# respirhoCR2450.net
KiCad netlist of a schematic drawn in EAGLE
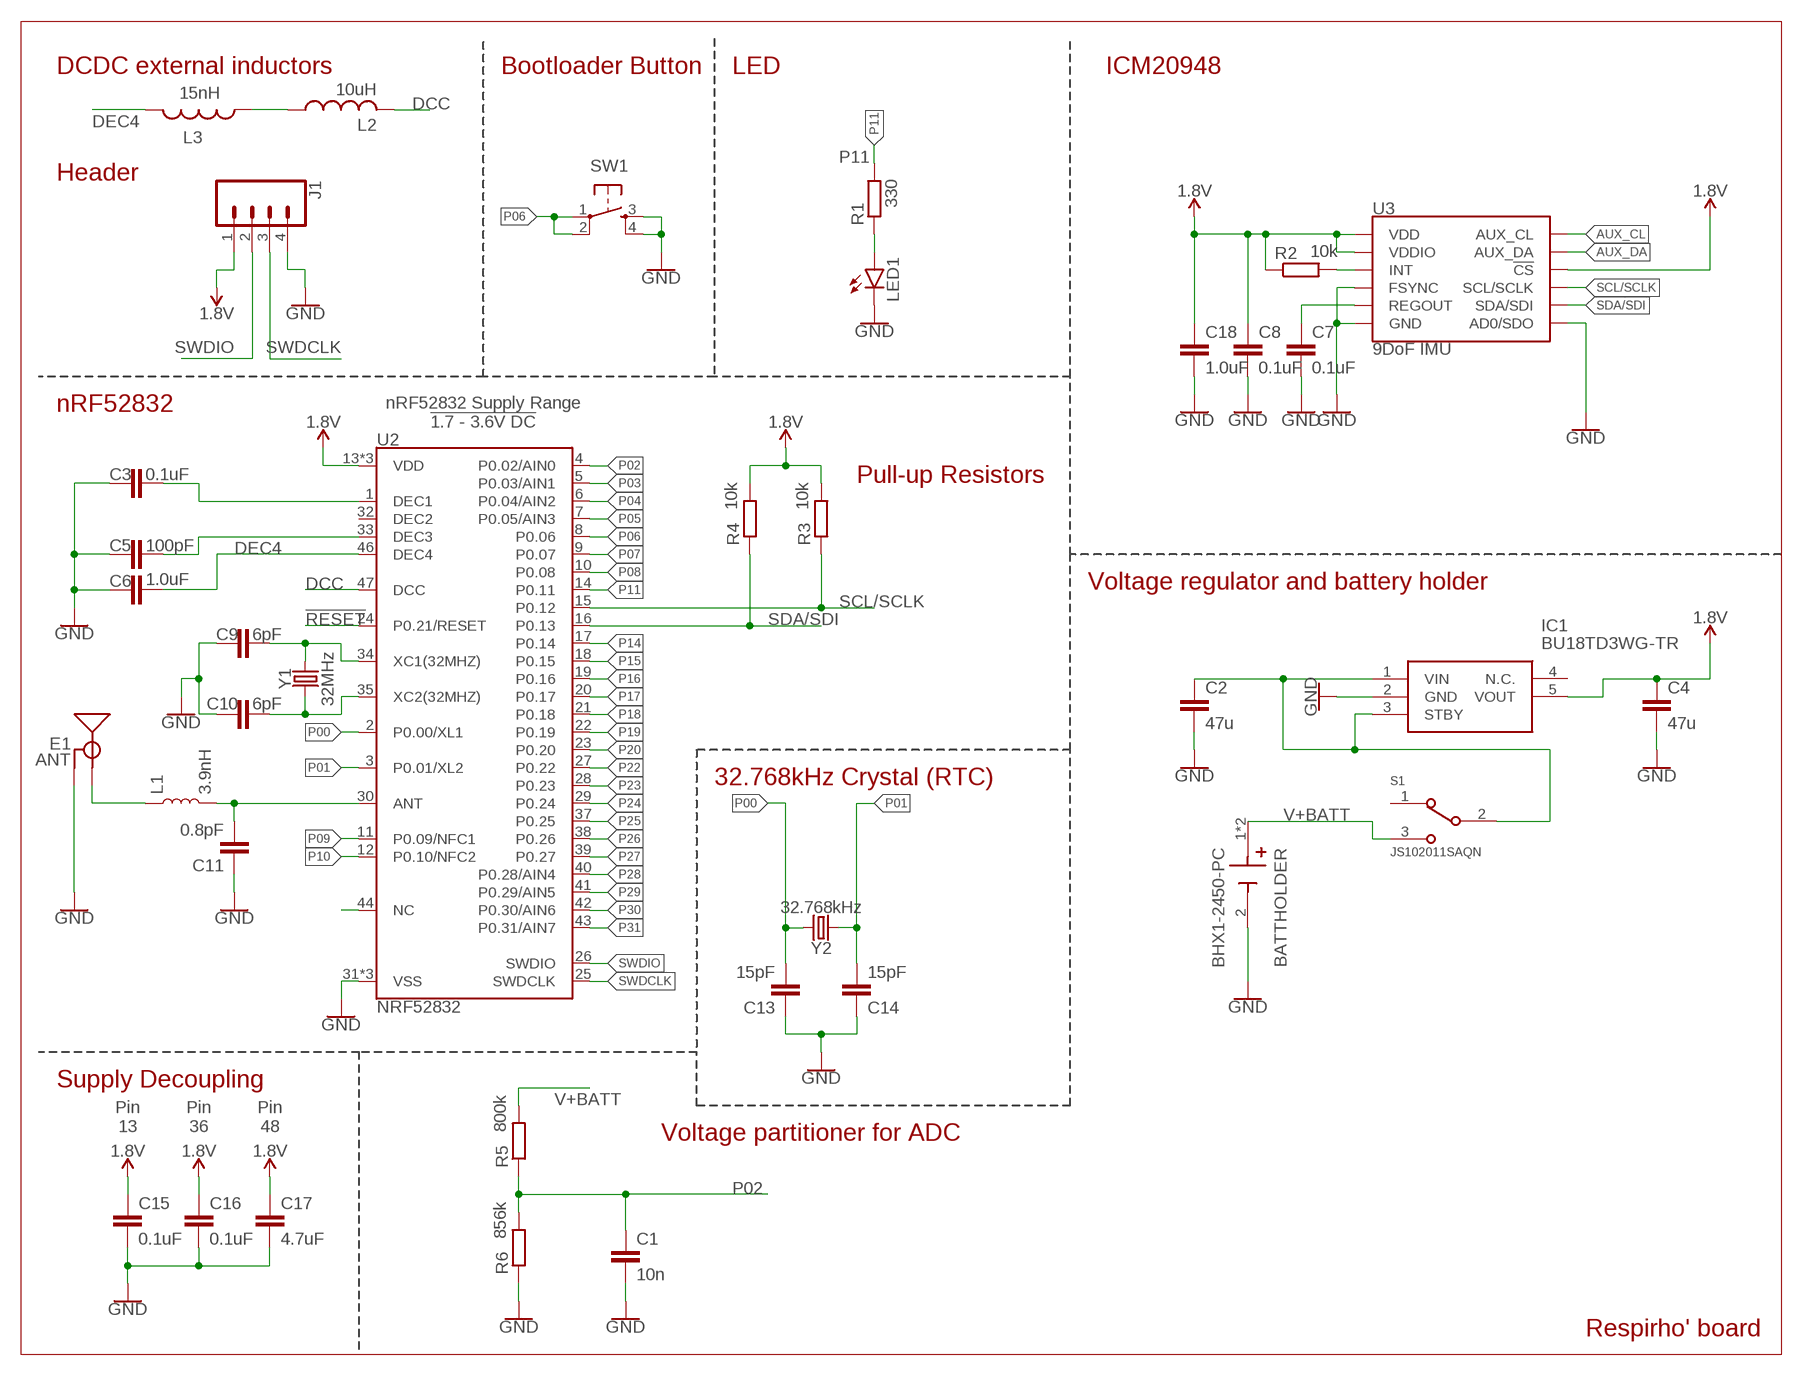
[diagram p0: schematic, sheet 1]

(export (version "E")
  (design (tool "Eeschema 10.0.6"))
  (components
    (comp (ref "BATTHOLDER")
      (value "BHX1-2450-PC")
      (footprint "eagle-import:BAT_BHX1-2450-PC")
      (fields (field (name "DIGI-KEY_PART_NUMBER") "BHX1-2450-PC-ND") (field (name "MF") "MPD"))
      (libsource (lib "eagle-import") (part "BHX1-2450-PC"))
    )
    (comp (ref "C1")
      (value "10n")
      (footprint "eagle-import:C1206")
      (libsource (lib "eagle-import") (part "C-EUC1206"))
    )
    (comp (ref "C2")
      (value "47u")
      (footprint "eagle-import:C1206")
      (libsource (lib "eagle-import") (part "C-EUC1206"))
    )
    (comp (ref "C3")
      (value "0.1uF")
      (footprint "eagle-import:0402")
      (libsource (lib "eagle-import") (part "0.1UF-0402-16V-10%"))
    )
    (comp (ref "C4")
      (value "47u")
      (footprint "eagle-import:C1206")
      (libsource (lib "eagle-import") (part "C-EUC1206"))
    )
    (comp (ref "C5")
      (value "100pF")
      (footprint "eagle-import:0402")
      (libsource (lib "eagle-import") (part "100PF-0402-50V-5%"))
    )
    (comp (ref "C6")
      (value "1.0uF")
      (footprint "eagle-import:0402")
      (libsource (lib "eagle-import") (part "1.0UF-0402-16V-10%"))
    )
    (comp (ref "C7")
      (value "0.1uF")
      (footprint "eagle-import:0603")
      (libsource (lib "eagle-import") (part "0.1UF-0603-25V-5%"))
    )
    (comp (ref "C8")
      (value "0.1uF")
      (footprint "eagle-import:0603")
      (libsource (lib "eagle-import") (part "0.1UF-0603-25V-5%"))
    )
    (comp (ref "C9")
      (value "6pF")
      (footprint "eagle-import:0402")
      (libsource (lib "eagle-import") (part "6PF-0402-50V-0.5%"))
    )
    (comp (ref "C10")
      (value "6pF")
      (footprint "eagle-import:0402")
      (libsource (lib "eagle-import") (part "6PF-0402-50V-0.5%"))
    )
    (comp (ref "C11")
      (value "0.8pF")
      (footprint "eagle-import:0402")
      (libsource (lib "eagle-import") (part "0.8PF-0402-50V-0.1PF"))
    )
    (comp (ref "C13")
      (value "15pF")
      (footprint "eagle-import:0402")
      (libsource (lib "eagle-import") (part "15PF-0402-50V-5%"))
    )
    (comp (ref "C14")
      (value "15pF")
      (footprint "eagle-import:0402")
      (libsource (lib "eagle-import") (part "15PF-0402-50V-5%"))
    )
    (comp (ref "C15")
      (value "0.1uF")
      (footprint "eagle-import:0402")
      (libsource (lib "eagle-import") (part "0.1UF-0402-16V-10%"))
    )
    (comp (ref "C16")
      (value "0.1uF")
      (footprint "eagle-import:0402")
      (libsource (lib "eagle-import") (part "0.1UF-0402-16V-10%"))
    )
    (comp (ref "C17")
      (value "4.7uF")
      (footprint "eagle-import:0603")
      (libsource (lib "eagle-import") (part "4.7UF0603"))
    )
    (comp (ref "C18")
      (value "1.0uF")
      (footprint "eagle-import:0603")
      (libsource (lib "eagle-import") (part "1.0UF-0603-16V-10%-X7R"))
    )
    (comp (ref "E1")
      (value "ANT")
      (footprint "eagle-import:TRACE_ANTENNA_2.4GHZ_15.2MM")
      (libsource (lib "eagle-import") (part "ANTENNA-GROUNDEDTRACE-15.2MM"))
    )
    (comp (ref "IC1")
      (value "BU18TD3WG-TR")
      (footprint "eagle-import:SOT95P280X125-5N")
      (fields (field (name "MOUSER_PART_NUMBER") "755-BU18TD3WG-TR"))
      (libsource (lib "eagle-import") (part "BU18TD3WG-TR"))
    )
    (comp (ref "J1")
      (value "CONN_04PTH")
      (footprint "eagle-import:1X04")
      (libsource (lib "eagle-import") (part "CONN_04PTH"))
    )
    (comp (ref "L1")
      (value "3.9nH")
      (footprint "eagle-import:0402")
      (libsource (lib "eagle-import") (part "INDUCTOR-0402-3.9NH"))
    )
    (comp (ref "L2")
      (value "10uH")
      (footprint "eagle-import:RESC0603_L")
      (libsource (lib "eagle-import") (part "INDUCTOR_0603_L"))
    )
    (comp (ref "L3")
      (value "15nH")
      (footprint "eagle-import:INDC1005X55N")
      (fields
        (field (name "DIGI-KEY_PART_NUMBER") "490-2625-1-ND")
        (field (name "MF") "Murata Electronics")
        (field (name "MP") "LQG15HS15NJ02D")
      )
      (libsource (lib "eagle-import") (part "LQG15HS15NJ02D"))
    )
    (comp (ref "LED1")
      (value "LEDCHIPLED_1206")
      (footprint "eagle-import:CHIPLED_1206")
      (libsource (lib "eagle-import") (part "LEDCHIPLED_1206"))
    )
    (comp (ref "R1")
      (value "330")
      (footprint "eagle-import:R0805")
      (libsource (lib "eagle-import") (part "R-EU_R0805"))
    )
    (comp (ref "R2")
      (value "10k")
      (footprint "eagle-import:R0805")
      (libsource (lib "eagle-import") (part "R-EU_R0805"))
    )
    (comp (ref "R3")
      (value "10k")
      (footprint "eagle-import:R0805")
      (libsource (lib "eagle-import") (part "R-EU_R0805"))
    )
    (comp (ref "R4")
      (value "10k")
      (footprint "eagle-import:R0805")
      (libsource (lib "eagle-import") (part "R-EU_R0805"))
    )
    (comp (ref "R5")
      (value "800k")
      (footprint "eagle-import:R0805")
      (libsource (lib "eagle-import") (part "R-EU_R0805"))
    )
    (comp (ref "R6")
      (value "856k")
      (footprint "eagle-import:R0805")
      (libsource (lib "eagle-import") (part "R-EU_R0805"))
    )
    (comp (ref "S1")
      (value "JS102011SAQN")
      (footprint "eagle-import:SW_JS102011SAQN")
      (fields (field (name "DIGI-KEY_PART_NUMBER") "401-1999-1-ND") (field (name "MF") "C&K"))
      (libsource (lib "eagle-import") (part "JS102011SAQN"))
    )
    (comp (ref "SW1")
      (value "SWITCH_SPST_4_PINRECT")
      (footprint "eagle-import:TACTILE_SWITCH_SMD_4.6X2.8MM")
      (libsource (lib "eagle-import") (part "SWITCH_SPST_4_PINRECT"))
    )
    (comp (ref "U2")
      (value "NRF52832")
      (footprint "eagle-import:QFN48-6X6MM")
      (libsource (lib "eagle-import") (part "NRF52832"))
    )
    (comp (ref "U3")
      (value "9DoF IMU")
      (footprint "eagle-import:QFN24-3X3")
      (libsource (lib "eagle-import") (part "ICM-20948"))
    )
    (comp (ref "Y1")
      (value "32MHz")
      (footprint "eagle-import:CRYSTAL-SMD-2.0X1.6MM")
      (libsource (lib "eagle-import") (part "CRYSTAL-32MHZ-SMD-2.0X1.6MM"))
    )
    (comp (ref "Y2")
      (value "32.768kHz")
      (footprint "eagle-import:CRYSTAL-SMD-3.2X1.5MM")
      (libsource (lib "eagle-import") (part "CRYSTAL-32.768KHZSMD-3.2X1.5"))
    )
  )
  (nets
    (net (code "1") (name "/DCC") (class "Default")
      (node (ref "L2") (pin "2") (pinfunction "2_2") (pintype "passive"))
      (node (ref "U2") (pin "47") (pinfunction "DCC_47") (pintype "bidirectional"))
    )
    (net (code "2") (name "/DEC4") (class "Default")
      (node (ref "C6") (pin "2") (pinfunction "2_2") (pintype "passive"))
      (node (ref "L3") (pin "2") (pinfunction "2_2") (pintype "passive"))
      (node (ref "U2") (pin "46") (pinfunction "DEC4_46") (pintype "bidirectional"))
    )
    (net (code "3") (name "/V+BATT") (class "Default")
      (node (ref "BATTHOLDER") (pin "1") (pinfunction "+_1") (pintype "passive"))
      (node (ref "BATTHOLDER") (pin "1_1") (pinfunction "+_1_1") (pintype "passive"))
      (node (ref "R5") (pin "2") (pinfunction "2_2") (pintype "passive"))
      (node (ref "S1") (pin "3") (pinfunction "3_3") (pintype "passive"))
    )
    (net (code "4") (name "/~{RESET}") (class "Default")
      (node (ref "U2") (pin "24") (pinfunction "P0.21/RESET_24") (pintype "bidirectional"))
    )
    (net (code "5") (name "1.8V") (class "Default")
      (node (ref "C15") (pin "1") (pinfunction "1_1") (pintype "passive"))
      (node (ref "C16") (pin "1") (pinfunction "1_1") (pintype "passive"))
      (node (ref "C17") (pin "1") (pinfunction "1_1") (pintype "passive"))
      (node (ref "C18") (pin "1") (pinfunction "1_1") (pintype "passive"))
      (node (ref "C4") (pin "1") (pinfunction "1_1") (pintype "passive"))
      (node (ref "C8") (pin "1") (pinfunction "1_1") (pintype "passive"))
      (node (ref "IC1") (pin "5") (pinfunction "VOUT_5") (pintype "bidirectional"))
      (node (ref "J1") (pin "1") (pinfunction "1_1") (pintype "passive"))
      (node (ref "R2") (pin "1") (pinfunction "1_1") (pintype "passive"))
      (node (ref "R3") (pin "2") (pinfunction "2_2") (pintype "passive"))
      (node (ref "R4") (pin "2") (pinfunction "2_2") (pintype "passive"))
      (node (ref "U2") (pin "13") (pinfunction "VDD_13") (pintype "bidirectional"))
      (node (ref "U2") (pin "36") (pinfunction "VDD_36") (pintype "bidirectional"))
      (node (ref "U2") (pin "48") (pinfunction "VDD_48") (pintype "bidirectional"))
      (node (ref "U3") (pin "13") (pinfunction "VDD_13") (pintype "bidirectional"))
      (node (ref "U3") (pin "22") (pinfunction "~{CS}_22") (pintype "bidirectional"))
      (node (ref "U3") (pin "8") (pinfunction "VDDIO_8") (pintype "bidirectional"))
    )
    (net (code "6") (name "AUX_CL") (class "Default")
      (node (ref "U3") (pin "7") (pinfunction "AUX_CL_7") (pintype "bidirectional"))
    )
    (net (code "7") (name "AUX_DA") (class "Default")
      (node (ref "U3") (pin "21") (pinfunction "AUX_DA_21") (pintype "bidirectional"))
    )
    (net (code "8") (name "GND") (class "Default")
      (node (ref "BATTHOLDER") (pin "2") (pinfunction "-_2") (pintype "passive"))
      (node (ref "C1") (pin "2") (pinfunction "2_2") (pintype "passive"))
      (node (ref "C10") (pin "2") (pinfunction "2_2") (pintype "passive"))
      (node (ref "C11") (pin "1") (pinfunction "1_1") (pintype "passive"))
      (node (ref "C13") (pin "1") (pinfunction "1_1") (pintype "passive"))
      (node (ref "C14") (pin "1") (pinfunction "1_1") (pintype "passive"))
      (node (ref "C15") (pin "2") (pinfunction "2_2") (pintype "passive"))
      (node (ref "C16") (pin "2") (pinfunction "2_2") (pintype "passive"))
      (node (ref "C17") (pin "2") (pinfunction "2_2") (pintype "passive"))
      (node (ref "C18") (pin "2") (pinfunction "2_2") (pintype "passive"))
      (node (ref "C2") (pin "2") (pinfunction "2_2") (pintype "passive"))
      (node (ref "C3") (pin "1") (pinfunction "1_1") (pintype "passive"))
      (node (ref "C4") (pin "2") (pinfunction "2_2") (pintype "passive"))
      (node (ref "C5") (pin "1") (pinfunction "1_1") (pintype "passive"))
      (node (ref "C6") (pin "1") (pinfunction "1_1") (pintype "passive"))
      (node (ref "C7") (pin "2") (pinfunction "2_2") (pintype "passive"))
      (node (ref "C8") (pin "2") (pinfunction "2_2") (pintype "passive"))
      (node (ref "C9") (pin "1") (pinfunction "1_1") (pintype "passive"))
      (node (ref "E1") (pin "GND") (pinfunction "GND_GND") (pintype "bidirectional"))
      (node (ref "IC1") (pin "2") (pinfunction "GND_2") (pintype "bidirectional"))
      (node (ref "J1") (pin "4") (pinfunction "4_4") (pintype "passive"))
      (node (ref "LED1") (pin "C") (pinfunction "C_C") (pintype "passive"))
      (node (ref "R6") (pin "1") (pinfunction "1_1") (pintype "passive"))
      (node (ref "SW1") (pin "3") (pinfunction "3_3") (pintype "passive"))
      (node (ref "SW1") (pin "4") (pinfunction "4_4") (pintype "passive"))
      (node (ref "U2") (pin "31") (pinfunction "VSS_31") (pintype "bidirectional"))
      (node (ref "U2") (pin "45") (pinfunction "VSS_45") (pintype "bidirectional"))
      (node (ref "U2") (pin "EP") (pinfunction "VSS_EP") (pintype "bidirectional"))
      (node (ref "U3") (pin "11") (pinfunction "FSYNC_11") (pintype "bidirectional"))
      (node (ref "U3") (pin "18") (pinfunction "GND_18") (pintype "bidirectional"))
      (node (ref "U3") (pin "20") (pinfunction "GND_20") (pintype "bidirectional"))
      (node (ref "U3") (pin "9") (pinfunction "AD0/SDO_9") (pintype "bidirectional"))
    )
    (net (code "9") (name "Net-(E1-SIGNAL)") (class "Default")
      (node (ref "E1") (pin "ANT") (pinfunction "SIGNAL_ANT") (pintype "bidirectional"))
      (node (ref "L1") (pin "1") (pinfunction "1_1") (pintype "passive"))
    )
    (net (code "10") (name "Net-(IC1-STBY)") (class "Default")
      (node (ref "C2") (pin "1") (pinfunction "1_1") (pintype "passive"))
      (node (ref "IC1") (pin "1") (pinfunction "VIN_1") (pintype "bidirectional"))
      (node (ref "IC1") (pin "3") (pinfunction "STBY_3") (pintype "bidirectional"))
      (node (ref "S1") (pin "2") (pinfunction "2_2") (pintype "passive"))
    )
    (net (code "11") (name "Net-(L2-Pad1)") (class "Default")
      (node (ref "L2") (pin "1") (pinfunction "1_1") (pintype "passive"))
      (node (ref "L3") (pin "1") (pinfunction "1_1") (pintype "passive"))
    )
    (net (code "12") (name "Net-(LED1-PadA)") (class "Default")
      (node (ref "LED1") (pin "A") (pinfunction "A_A") (pintype "passive"))
      (node (ref "R1") (pin "1") (pinfunction "1_1") (pintype "passive"))
    )
    (net (code "13") (name "Net-(U2-ANT)") (class "Default")
      (node (ref "C11") (pin "2") (pinfunction "2_2") (pintype "passive"))
      (node (ref "L1") (pin "2") (pinfunction "2_2") (pintype "passive"))
      (node (ref "U2") (pin "30") (pinfunction "ANT_30") (pintype "bidirectional"))
    )
    (net (code "14") (name "Net-(U2-DEC1)") (class "Default")
      (node (ref "C3") (pin "2") (pinfunction "2_2") (pintype "passive"))
      (node (ref "U2") (pin "1") (pinfunction "DEC1_1") (pintype "bidirectional"))
    )
    (net (code "15") (name "Net-(U2-DEC3)") (class "Default")
      (node (ref "C5") (pin "2") (pinfunction "2_2") (pintype "passive"))
      (node (ref "U2") (pin "33") (pinfunction "DEC3_33") (pintype "bidirectional"))
    )
    (net (code "16") (name "Net-(U2-XC1(32MHZ))") (class "Default")
      (node (ref "C9") (pin "2") (pinfunction "2_2") (pintype "passive"))
      (node (ref "U2") (pin "34") (pinfunction "XC1(32MHZ)_34") (pintype "bidirectional"))
      (node (ref "Y1") (pin "3") (pinfunction "2_3") (pintype "passive"))
    )
    (net (code "17") (name "Net-(U2-XC2(32MHZ))") (class "Default")
      (node (ref "C10") (pin "1") (pinfunction "1_1") (pintype "passive"))
      (node (ref "U2") (pin "35") (pinfunction "XC2(32MHZ)_35") (pintype "bidirectional"))
      (node (ref "Y1") (pin "1") (pinfunction "1_1") (pintype "passive"))
    )
    (net (code "18") (name "Net-(U3-INT)") (class "Default")
      (node (ref "R2") (pin "2") (pinfunction "2_2") (pintype "passive"))
      (node (ref "U3") (pin "12") (pinfunction "INT_12") (pintype "bidirectional"))
    )
    (net (code "19") (name "Net-(U3-REGOUT)") (class "Default")
      (node (ref "C7") (pin "1") (pinfunction "1_1") (pintype "passive"))
      (node (ref "U3") (pin "10") (pinfunction "REGOUT_10") (pintype "bidirectional"))
    )
    (net (code "20") (name "P00") (class "Default")
      (node (ref "C13") (pin "2") (pinfunction "2_2") (pintype "passive"))
      (node (ref "U2") (pin "2") (pinfunction "P0.00/XL1_2") (pintype "bidirectional"))
      (node (ref "Y2") (pin "P$2") (pinfunction "2_P$2") (pintype "passive"))
    )
    (net (code "21") (name "P01") (class "Default")
      (node (ref "C14") (pin "2") (pinfunction "2_2") (pintype "passive"))
      (node (ref "U2") (pin "3") (pinfunction "P0.01/XL2_3") (pintype "bidirectional"))
      (node (ref "Y2") (pin "P$1") (pinfunction "1_P$1") (pintype "passive"))
    )
    (net (code "22") (name "P02") (class "Default")
      (node (ref "C1") (pin "1") (pinfunction "1_1") (pintype "passive"))
      (node (ref "R5") (pin "1") (pinfunction "1_1") (pintype "passive"))
      (node (ref "R6") (pin "2") (pinfunction "2_2") (pintype "passive"))
      (node (ref "U2") (pin "4") (pinfunction "P0.02/AIN0_4") (pintype "bidirectional"))
    )
    (net (code "23") (name "P03") (class "Default")
      (node (ref "U2") (pin "5") (pinfunction "P0.03/AIN1_5") (pintype "bidirectional"))
    )
    (net (code "24") (name "P04") (class "Default")
      (node (ref "U2") (pin "6") (pinfunction "P0.04/AIN2_6") (pintype "bidirectional"))
    )
    (net (code "25") (name "P05") (class "Default")
      (node (ref "U2") (pin "7") (pinfunction "P0.05/AIN3_7") (pintype "bidirectional"))
    )
    (net (code "26") (name "P06") (class "Default")
      (node (ref "SW1") (pin "1") (pinfunction "1_1") (pintype "passive"))
      (node (ref "SW1") (pin "2") (pinfunction "2_2") (pintype "passive"))
      (node (ref "U2") (pin "8") (pinfunction "P0.06_8") (pintype "bidirectional"))
    )
    (net (code "27") (name "P07") (class "Default")
      (node (ref "U2") (pin "9") (pinfunction "P0.07_9") (pintype "bidirectional"))
    )
    (net (code "28") (name "P08") (class "Default")
      (node (ref "U2") (pin "10") (pinfunction "P0.08_10") (pintype "bidirectional"))
    )
    (net (code "29") (name "P09") (class "Default")
      (node (ref "U2") (pin "11") (pinfunction "P0.09/NFC1_11") (pintype "bidirectional"))
    )
    (net (code "30") (name "P10") (class "Default")
      (node (ref "U2") (pin "12") (pinfunction "P0.10/NFC2_12") (pintype "bidirectional"))
    )
    (net (code "31") (name "P11") (class "Default")
      (node (ref "R1") (pin "2") (pinfunction "2_2") (pintype "passive"))
      (node (ref "U2") (pin "14") (pinfunction "P0.11_14") (pintype "bidirectional"))
    )
    (net (code "32") (name "P14") (class "Default")
      (node (ref "U2") (pin "17") (pinfunction "P0.14_17") (pintype "bidirectional"))
    )
    (net (code "33") (name "P15") (class "Default")
      (node (ref "U2") (pin "18") (pinfunction "P0.15_18") (pintype "bidirectional"))
    )
    (net (code "34") (name "P16") (class "Default")
      (node (ref "U2") (pin "19") (pinfunction "P0.16_19") (pintype "bidirectional"))
    )
    (net (code "35") (name "P17") (class "Default")
      (node (ref "U2") (pin "20") (pinfunction "P0.17_20") (pintype "bidirectional"))
    )
    (net (code "36") (name "P18") (class "Default")
      (node (ref "U2") (pin "21") (pinfunction "P0.18_21") (pintype "bidirectional"))
    )
    (net (code "37") (name "P19") (class "Default")
      (node (ref "U2") (pin "22") (pinfunction "P0.19_22") (pintype "bidirectional"))
    )
    (net (code "38") (name "P20") (class "Default")
      (node (ref "U2") (pin "23") (pinfunction "P0.20_23") (pintype "bidirectional"))
    )
    (net (code "39") (name "P22") (class "Default")
      (node (ref "U2") (pin "27") (pinfunction "P0.22_27") (pintype "bidirectional"))
    )
    (net (code "40") (name "P23") (class "Default")
      (node (ref "U2") (pin "28") (pinfunction "P0.23_28") (pintype "bidirectional"))
    )
    (net (code "41") (name "P24") (class "Default")
      (node (ref "U2") (pin "29") (pinfunction "P0.24_29") (pintype "bidirectional"))
    )
    (net (code "42") (name "P25") (class "Default")
      (node (ref "U2") (pin "37") (pinfunction "P0.25_37") (pintype "bidirectional"))
    )
    (net (code "43") (name "P26") (class "Default")
      (node (ref "U2") (pin "38") (pinfunction "P0.26_38") (pintype "bidirectional"))
    )
    (net (code "44") (name "P27") (class "Default")
      (node (ref "U2") (pin "39") (pinfunction "P0.27_39") (pintype "bidirectional"))
    )
    (net (code "45") (name "P28") (class "Default")
      (node (ref "U2") (pin "40") (pinfunction "P0.28/AIN4_40") (pintype "bidirectional"))
    )
    (net (code "46") (name "P29") (class "Default")
      (node (ref "U2") (pin "41") (pinfunction "P0.29/AIN5_41") (pintype "bidirectional"))
    )
    (net (code "47") (name "P30") (class "Default")
      (node (ref "U2") (pin "42") (pinfunction "P0.30/AIN6_42") (pintype "bidirectional"))
    )
    (net (code "48") (name "P31") (class "Default")
      (node (ref "U2") (pin "43") (pinfunction "P0.31/AIN7_43") (pintype "bidirectional"))
    )
    (net (code "49") (name "SCL{slash}SCLK") (class "Default")
      (node (ref "R3") (pin "1") (pinfunction "1_1") (pintype "passive"))
      (node (ref "U2") (pin "15") (pinfunction "P0.12_15") (pintype "bidirectional"))
      (node (ref "U3") (pin "23") (pinfunction "SCL/SCLK_23") (pintype "bidirectional"))
    )
    (net (code "50") (name "SDA{slash}SDI") (class "Default")
      (node (ref "R4") (pin "1") (pinfunction "1_1") (pintype "passive"))
      (node (ref "U2") (pin "16") (pinfunction "P0.13_16") (pintype "bidirectional"))
      (node (ref "U3") (pin "24") (pinfunction "SDA/SDI_24") (pintype "bidirectional"))
    )
    (net (code "51") (name "SWDCLK") (class "Default")
      (node (ref "J1") (pin "3") (pinfunction "3_3") (pintype "passive"))
      (node (ref "U2") (pin "25") (pinfunction "SWDCLK_25") (pintype "bidirectional"))
    )
    (net (code "52") (name "SWDIO") (class "Default")
      (node (ref "J1") (pin "2") (pinfunction "2_2") (pintype "passive"))
      (node (ref "U2") (pin "26") (pinfunction "SWDIO_26") (pintype "bidirectional"))
    )
    (net (code "53") (name "unconnected-(IC1-N.C.-Pad4)") (class "Default")
      (node (ref "IC1") (pin "4") (pinfunction "N.C._4") (pintype "no_connect"))
    )
    (net (code "54") (name "unconnected-(S1-Pad1)") (class "Default")
      (node (ref "S1") (pin "1") (pinfunction "1_1") (pintype "passive"))
    )
    (net (code "55") (name "unconnected-(U2-DEC2-Pad32)") (class "Default")
      (node (ref "U2") (pin "32") (pinfunction "DEC2_32") (pintype "bidirectional"))
    )
    (net (code "56") (name "unconnected-(U2-NC-Pad44)") (class "Default")
      (node (ref "U2") (pin "44") (pinfunction "NC_44") (pintype "bidirectional"))
    )
  )
)
